# usb-cereal-cp-sch.net
KiCad netlist of a schematic drawn in Altium Designer
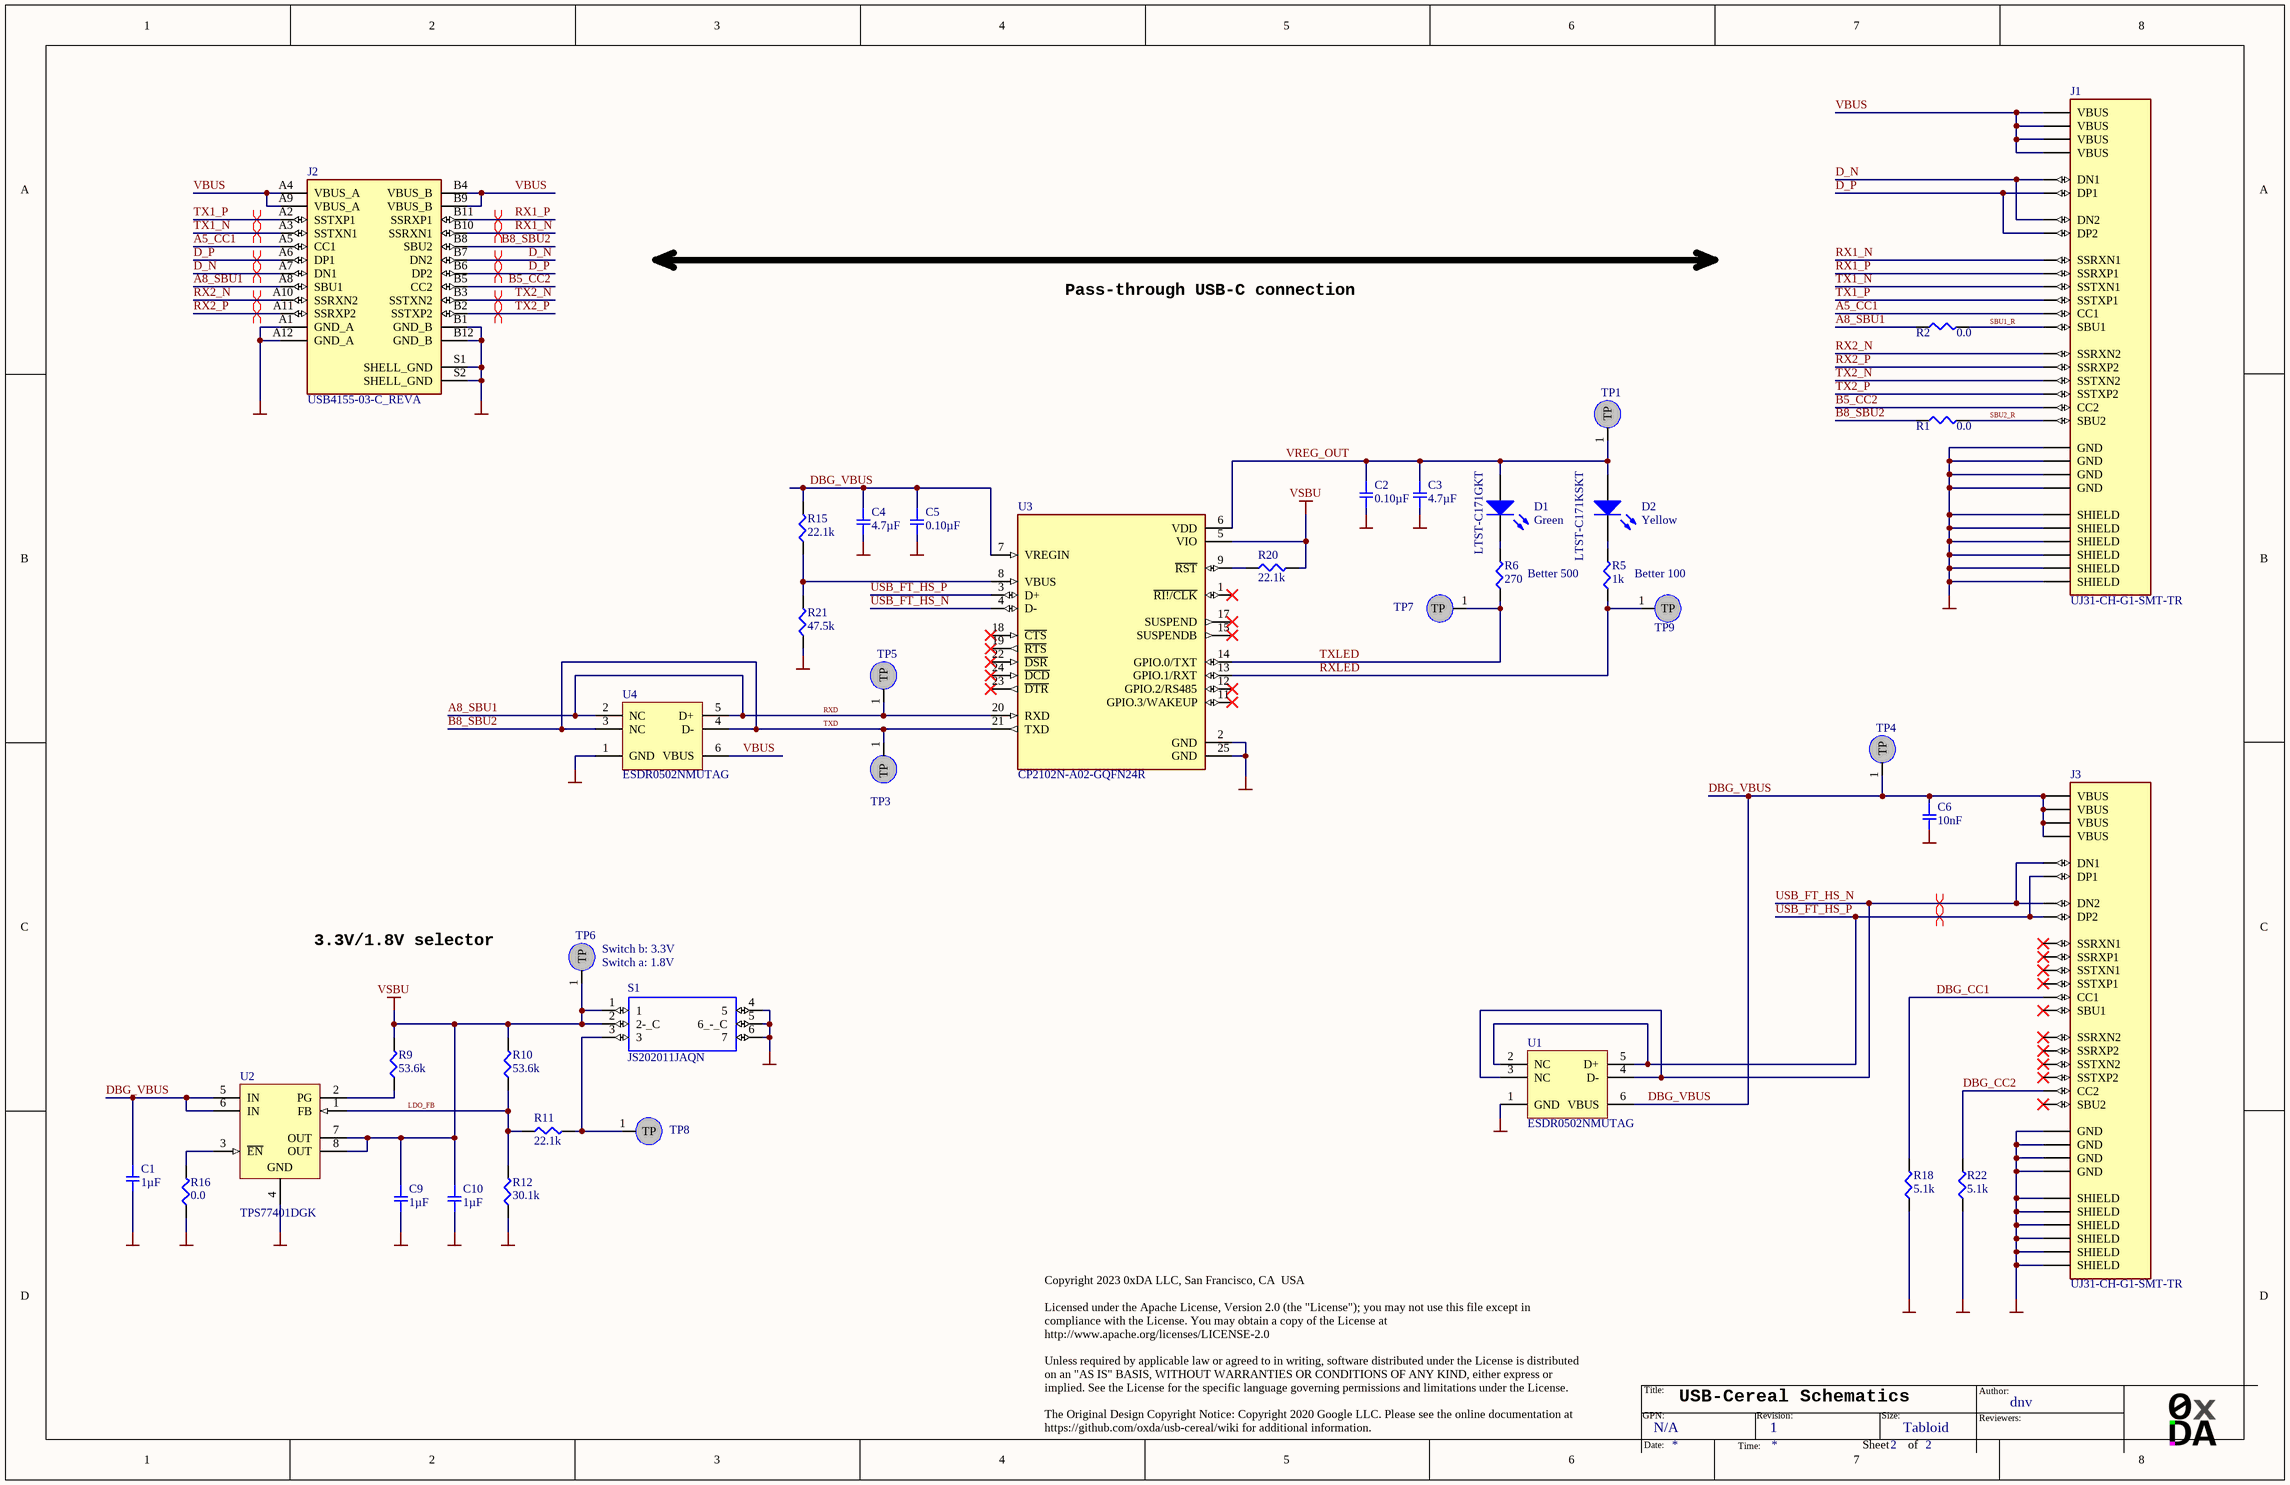
[diagram p0: usb-cereal-cp-sch.SchDoc]

(export (version "E")
  (design (tool "Eeschema 10.0.6"))
  (components
    (comp (ref "C1")
      (value "1µF")
      (footprint "SMD-0402C")
      (description "CAP CER 1UF 10V X7S 0402")
      (fields
        (field (name "DIGI-KEY PART NUMBER") "490-13409-1-ND")
        (field (name "PART NUMBER") "GCM155C71A105KE38D")
      )
      (libsource (lib "cap_murata_0402") (part "GCM155C71A105KE38D"))
    )
    (comp (ref "C2")
      (value "0.10µF")
      (footprint "SMD-0402C")
      (description "CAP CER 0.1UF 10V X5R 0402")
      (fields
        (field (name "DIGI-KEY PART NUMBER") "490-10008-1-ND")
        (field (name "PART NUMBER") "GRM152R61A104KE19D")
      )
      (libsource (lib "cap_murata_0402") (part "GRM152R61A104KE19D"))
    )
    (comp (ref "C3")
      (value "4.7µF")
      (footprint "SMD-0402C")
      (description "CAP CER 4.7UF 10V X5R 0402")
      (fields
        (field (name "DIGI-KEY PART NUMBER") "490-13252-1-ND")
        (field (name "PART NUMBER") "ZRB15XR61A475KE01D")
      )
      (libsource (lib "cap_murata_0402") (part "ZRB15XR61A475KE01D"))
    )
    (comp (ref "C4")
      (value "4.7µF")
      (footprint "SMD-0402C")
      (description "CAP CER 4.7UF 10V X5R 0402")
      (fields
        (field (name "DIGI-KEY PART NUMBER") "490-13252-1-ND")
        (field (name "PART NUMBER") "ZRB15XR61A475KE01D")
      )
      (libsource (lib "cap_murata_0402") (part "ZRB15XR61A475KE01D"))
    )
    (comp (ref "C5")
      (value "0.10µF")
      (footprint "SMD-0402C")
      (description "CAP CER 0.1UF 10V X5R 0402")
      (fields
        (field (name "DIGI-KEY PART NUMBER") "490-10008-1-ND")
        (field (name "PART NUMBER") "GRM152R61A104KE19D")
      )
      (libsource (lib "cap_murata_0402") (part "GRM152R61A104KE19D"))
    )
    (comp (ref "C6")
      (value "10nF")
      (footprint "SMD-0402C")
      (description "CAP CER 10000PF 25V X7R 0402")
      (fields
        (field (name "DIGI-KEY PART NUMBER") "490-6043-1-ND")
        (field (name "PART NUMBER") "GCM155R71E103KA37D")
      )
      (libsource (lib "cap_murata_0402") (part "GCM155R71E103KA37D"))
    )
    (comp (ref "C9")
      (value "1µF")
      (footprint "SMD-0402C")
      (description "CAP CER 1UF 10V X7S 0402")
      (fields
        (field (name "DIGI-KEY PART NUMBER") "490-13409-1-ND")
        (field (name "PART NUMBER") "GCM155C71A105KE38D")
      )
      (libsource (lib "cap_murata_0402") (part "GCM155C71A105KE38D"))
    )
    (comp (ref "C10")
      (value "1µF")
      (footprint "SMD-0402C")
      (description "CAP CER 1UF 10V X7S 0402")
      (fields
        (field (name "DIGI-KEY PART NUMBER") "490-13409-1-ND")
        (field (name "PART NUMBER") "GCM155C71A105KE38D")
      )
      (libsource (lib "cap_murata_0402") (part "GCM155C71A105KE38D"))
    )
    (comp (ref "D1")
      (value "LTST-C171GKT")
      (footprint "0805")
      (description "LED")
      (fields (field (name "COLOR") "Green"))
      (libsource (lib "lite-on") (part "LTST-C171GKT"))
    )
    (comp (ref "D2")
      (value "LTST-C171KSKT")
      (footprint "0805")
      (description "LED")
      (fields (field (name "COLOR") "Yellow"))
      (libsource (lib "lite-on") (part "LTST-C171KSKT"))
    )
    (comp (ref "J1")
      (value "UJ31-CH-G1-SMT-TR")
      (footprint "SnapEDApcb:CUI_UJ31-CH-G1-SMT-TR")
      (description "Type C, USB 3.1 Gen 2, 5 A, Right Angle, Surface Mount _SMT_ , USB Receptacle")
      (fields (field (name "MF") "CUI Devices"))
      (libsource (lib "UJ31-CH-G1-SMT-TR") (part "UJ31-CH-G1-SMT-TR"))
    )
    (comp (ref "J2")
      (value "USB4155-03-C_REVA")
      (footprint "GCT_USB4155-03-C_REVA")
      (fields (field (name "MF") "Global Connector Technology") (field (name "MP") "USB4155-03-C"))
      (libsource (lib "USB4155-03-C_REVA") (part "USB4155-03-C_REVA"))
    )
    (comp (ref "J3")
      (value "UJ31-CH-G1-SMT-TR")
      (footprint "SnapEDApcb:CUI_UJ31-CH-G1-SMT-TR")
      (description "Type C, USB 3.1 Gen 2, 5 A, Right Angle, Surface Mount _SMT_ , USB Receptacle")
      (fields (field (name "MF") "CUI Devices"))
      (libsource (lib "UJ31-CH-G1-SMT-TR") (part "UJ31-CH-G1-SMT-TR"))
    )
    (comp (ref "R1")
      (value "0.0")
      (footprint "SMD-0402-RES")
      (description "RES SMD 0.0OHM JUMPER 1/10W 0402")
      (fields (field (name "PART NUMBER") "ERJ-2GE0R00X") (field (name "DIGI-KEY PART NUMBER") "P0.0JCT-ND"))
      (libsource (lib "res_0402_panasonic_ERJ") (part "ERJ-2GE0R00X"))
    )
    (comp (ref "R2")
      (value "0.0")
      (footprint "SMD-0402-RES")
      (description "RES SMD 0.0OHM JUMPER 1/10W 0402")
      (fields (field (name "PART NUMBER") "ERJ-2GE0R00X") (field (name "DIGI-KEY PART NUMBER") "P0.0JCT-ND"))
      (libsource (lib "res_0402_panasonic_ERJ") (part "ERJ-2GE0R00X"))
    )
    (comp (ref "R5")
      (value "1k")
      (footprint "SMD-0402-RES")
      (description "RES SMD 1K OHM 1% 1/5W 0402")
      (fields
        (field (name "PART NUMBER") "ERJ-PA2F1001X")
        (field (name "DIGI-KEY PART NUMBER") "P17224CT-ND")
      )
      (libsource (lib "res_0402_panasonic_ERJ") (part "ERJ-PA2F1001X"))
    )
    (comp (ref "R6")
      (value "270")
      (footprint "SMD-0402-RES")
      (description "RES SMD 270 OHM 1% 1/10W 0402")
      (fields (field (name "PART NUMBER") "ERJ-2RKF2700X") (field (name "DIGI-KEY PART NUMBER") "P270LCT-ND"))
      (libsource (lib "res_0402_panasonic_ERJ") (part "ERJ-2RKF2700X"))
    )
    (comp (ref "R9")
      (value "53.6k")
      (footprint "SMD-0402-RES")
      (description "RES SMD 53.6K OHM 1% 1/10W 0402")
      (fields
        (field (name "PART NUMBER") "ERJ-2RKF5362X")
        (field (name "DIGI-KEY PART NUMBER") "P53.6KLCT-ND")
      )
      (libsource (lib "res_0402_panasonic_ERJ") (part "ERJ-2RKF5362X"))
    )
    (comp (ref "R10")
      (value "53.6k")
      (footprint "SMD-0402-RES")
      (description "RES SMD 53.6K OHM 1% 1/10W 0402")
      (fields
        (field (name "PART NUMBER") "ERJ-2RKF5362X")
        (field (name "DIGI-KEY PART NUMBER") "P53.6KLCT-ND")
      )
      (libsource (lib "res_0402_panasonic_ERJ") (part "ERJ-2RKF5362X"))
    )
    (comp (ref "R11")
      (value "22.1k")
      (footprint "SMD-0402-RES")
      (description "RES SMD 22.1K OHM 1% 1/10W 0402")
      (fields
        (field (name "PART NUMBER") "ERJ-2RKF2212X")
        (field (name "DIGI-KEY PART NUMBER") "P22.1KLCT-ND")
      )
      (libsource (lib "res_0402_panasonic_ERJ") (part "ERJ-2RKF2212X"))
    )
    (comp (ref "R12")
      (value "30.1k")
      (footprint "SMD-0402-RES")
      (description "RES SMD 30.1K OHM 1% 1/10W 0402")
      (fields
        (field (name "PART NUMBER") "ERJ-2RKF3012X")
        (field (name "DIGI-KEY PART NUMBER") "P30.1KLCT-ND")
      )
      (libsource (lib "res_0402_panasonic_ERJ") (part "ERJ-2RKF3012X"))
    )
    (comp (ref "R15")
      (value "22.1k")
      (footprint "SMD-0402-RES")
      (description "RES SMD 22.1K OHM 1% 1/10W 0402")
      (fields
        (field (name "PART NUMBER") "ERJ-2RKF2212X")
        (field (name "DIGI-KEY PART NUMBER") "P22.1KLCT-ND")
      )
      (libsource (lib "res_0402_panasonic_ERJ") (part "ERJ-2RKF2212X"))
    )
    (comp (ref "R16")
      (value "0.0")
      (footprint "SMD-0402-RES")
      (description "RES SMD 0.0OHM JUMPER 1/10W 0402")
      (fields (field (name "PART NUMBER") "ERJ-2GE0R00X") (field (name "DIGI-KEY PART NUMBER") "P0.0JCT-ND"))
      (libsource (lib "res_0402_panasonic_ERJ") (part "ERJ-2GE0R00X"))
    )
    (comp (ref "R18")
      (value "5.1k")
      (footprint "SMD-0402-RES")
      (description "RES SMD 5.1K OHM 1% 1/10W 0402")
      (fields
        (field (name "PART NUMBER") "ERJ-2RKF5101X")
        (field (name "DIGI-KEY PART NUMBER") "P5.10KLCT-ND")
      )
      (libsource (lib "res_0402_panasonic_ERJ") (part "ERJ-2RKF5101X"))
    )
    (comp (ref "R20")
      (value "22.1k")
      (footprint "SMD-0402-RES")
      (description "RES SMD 22.1K OHM 1% 1/10W 0402")
      (fields
        (field (name "PART NUMBER") "ERJ-2RKF2212X")
        (field (name "DIGI-KEY PART NUMBER") "P22.1KLCT-ND")
      )
      (libsource (lib "res_0402_panasonic_ERJ") (part "ERJ-2RKF2212X"))
    )
    (comp (ref "R21")
      (value "47.5k")
      (footprint "SMD-0402-RES")
      (description "RES SMD 47.5K OHM 1% 1/10W 0402")
      (fields
        (field (name "PART NUMBER") "ERJ-2RKF4752X")
        (field (name "DIGI-KEY PART NUMBER") "P47.5KLCT-ND")
      )
      (libsource (lib "res_0402_panasonic_ERJ") (part "ERJ-2RKF4752X"))
    )
    (comp (ref "R22")
      (value "5.1k")
      (footprint "SMD-0402-RES")
      (description "RES SMD 5.1K OHM 1% 1/10W 0402")
      (fields
        (field (name "PART NUMBER") "ERJ-2RKF5101X")
        (field (name "DIGI-KEY PART NUMBER") "P5.10KLCT-ND")
      )
      (libsource (lib "res_0402_panasonic_ERJ") (part "ERJ-2RKF5101X"))
    )
    (comp (ref "S1")
      (value "JS202011JAQN")
      (footprint "JS202011JAQN")
      (description "Slide Switch DPDT Surface Mount, Right Angle")
      (fields (field (name "MF") "C&K"))
      (libsource (lib "JS202011JAQN") (part "JS202011JAQN"))
    )
    (comp (ref "TP1") (value "GND") (footprint "Testpoint") (libsource (lib "Misc") (part "Testpoint")))
    (comp (ref "TP3") (value "GND") (footprint "Testpoint") (libsource (lib "Misc") (part "Testpoint")))
    (comp (ref "TP4") (value "GND") (footprint "Testpoint") (libsource (lib "Misc") (part "Testpoint")))
    (comp (ref "TP5") (value "GND") (footprint "Testpoint") (libsource (lib "Misc") (part "Testpoint")))
    (comp (ref "TP6") (value "GND") (footprint "Testpoint") (libsource (lib "Misc") (part "Testpoint")))
    (comp (ref "TP7") (value "GND") (footprint "Testpoint") (libsource (lib "Misc") (part "Testpoint")))
    (comp (ref "TP8") (value "GND") (footprint "Testpoint") (libsource (lib "Misc") (part "Testpoint")))
    (comp (ref "TP9") (value "GND") (footprint "Testpoint") (libsource (lib "Misc") (part "Testpoint")))
    (comp (ref "U1")
      (value "ESDR0502NMUTAG")
      (footprint "ONSC-UDFN-6-517AA-01_V")
      (fields (field (name "MANUFACTURER") "On Semiconductor"))
      (libsource (lib "diode_esd_ON_Semi") (part "ESDR0502NMUTAG"))
    )
    (comp (ref "U2")
      (value "TPS77401DGK")
      (footprint "TI-DGK8_N")
      (fields (field (name "MANUFACTURER") "Texas Instruments"))
      (libsource (lib "ic_pwr_ldo_TI_single_channel_ldo_0-350mA") (part "TPS77401DGK"))
    )
    (comp (ref "U3")
      (value "CP2102N-A02-GQFN24R")
      (footprint "QFN50P400X400X80-25N")
      (description "USB Bridge, USB to UART USB 2.0 UART Interface 24-QFN _4x4_")
      (fields (field (name "MF") "Silicon Labs"))
      (libsource (lib "CP2102N-A02-GQFN24R") (part "CP2102N-A02-GQFN24R"))
    )
    (comp (ref "U4")
      (value "ESDR0502NMUTAG")
      (footprint "ONSC-UDFN-6-517AA-01_V")
      (fields (field (name "MANUFACTURER") "On Semiconductor"))
      (libsource (lib "diode_esd_ON_Semi") (part "ESDR0502NMUTAG"))
    )
  )
  (nets
    (net (code "1") (name "/A5_CC1") (class "Default")
      (node (ref "J1") (pin "A5") (pinfunction "CC1_A5") (pintype "bidirectional"))
      (node (ref "J2") (pin "A5") (pinfunction "CC1_A5") (pintype "bidirectional"))
    )
    (net (code "2") (name "/A8_SBU1") (class "Default")
      (node (ref "J2") (pin "A8") (pinfunction "SBU1_A8") (pintype "bidirectional"))
      (node (ref "R2") (pin "1") (pinfunction "1_1") (pintype "passive"))
      (node (ref "TP5") (pin "1") (pinfunction "TP_1") (pintype "passive"))
      (node (ref "U3") (pin "20") (pinfunction "RXD_20") (pintype "input"))
      (node (ref "U4") (pin "2") (pinfunction "NC_2") (pintype "passive"))
      (node (ref "U4") (pin "5") (pinfunction "D+_5") (pintype "passive"))
    )
    (net (code "3") (name "/B5_CC2") (class "Default")
      (node (ref "J1") (pin "B5") (pinfunction "CC2_B5") (pintype "bidirectional"))
      (node (ref "J2") (pin "B5") (pinfunction "CC2_B5") (pintype "bidirectional"))
    )
    (net (code "4") (name "/B8_SBU2") (class "Default")
      (node (ref "J2") (pin "B8") (pinfunction "SBU2_B8") (pintype "bidirectional"))
      (node (ref "R1") (pin "1") (pinfunction "1_1") (pintype "passive"))
      (node (ref "TP3") (pin "1") (pinfunction "TP_1") (pintype "passive"))
      (node (ref "U3") (pin "21") (pinfunction "TXD_21") (pintype "output"))
      (node (ref "U4") (pin "3") (pinfunction "NC_3") (pintype "passive"))
      (node (ref "U4") (pin "4") (pinfunction "D-_4") (pintype "passive"))
    )
    (net (code "5") (name "/DBG_CC1") (class "Default")
      (node (ref "J3") (pin "A5") (pinfunction "CC1_A5") (pintype "bidirectional"))
      (node (ref "R18") (pin "2") (pinfunction "2_2") (pintype "passive"))
    )
    (net (code "6") (name "/DBG_CC2") (class "Default")
      (node (ref "J3") (pin "B5") (pinfunction "CC2_B5") (pintype "bidirectional"))
      (node (ref "R22") (pin "2") (pinfunction "2_2") (pintype "passive"))
    )
    (net (code "7") (name "/DBG_VBUS") (class "Default")
      (node (ref "C1") (pin "1") (pinfunction "1_1") (pintype "passive"))
      (node (ref "C4") (pin "1") (pinfunction "1_1") (pintype "passive"))
      (node (ref "C5") (pin "1") (pinfunction "1_1") (pintype "passive"))
      (node (ref "C6") (pin "1") (pinfunction "1_1") (pintype "passive"))
      (node (ref "J3") (pin "A4") (pinfunction "VBUS_A4") (pintype "power_in"))
      (node (ref "J3") (pin "A9") (pinfunction "VBUS_A9") (pintype "power_in"))
      (node (ref "J3") (pin "B4") (pinfunction "VBUS_B4") (pintype "power_in"))
      (node (ref "J3") (pin "B9") (pinfunction "VBUS_B9") (pintype "power_in"))
      (node (ref "R15") (pin "2") (pinfunction "2_2") (pintype "passive"))
      (node (ref "TP4") (pin "1") (pinfunction "TP_1") (pintype "passive"))
      (node (ref "U1") (pin "6") (pinfunction "VBUS_6") (pintype "power_in"))
      (node (ref "U2") (pin "5") (pinfunction "IN_5") (pintype "power_in"))
      (node (ref "U2") (pin "6") (pinfunction "IN_6") (pintype "power_in"))
      (node (ref "U3") (pin "7") (pinfunction "VREGIN_7") (pintype "input"))
    )
    (net (code "8") (name "/D_N") (class "Default")
      (node (ref "J1") (pin "A7") (pinfunction "DN1_A7") (pintype "bidirectional"))
      (node (ref "J1") (pin "B7") (pinfunction "DN2_B7") (pintype "bidirectional"))
      (node (ref "J2") (pin "A7") (pinfunction "DN1_A7") (pintype "bidirectional"))
      (node (ref "J2") (pin "B7") (pinfunction "DN2_B7") (pintype "bidirectional"))
    )
    (net (code "9") (name "/D_P") (class "Default")
      (node (ref "J1") (pin "A6") (pinfunction "DP1_A6") (pintype "bidirectional"))
      (node (ref "J1") (pin "B6") (pinfunction "DP2_B6") (pintype "bidirectional"))
      (node (ref "J2") (pin "A6") (pinfunction "DP1_A6") (pintype "bidirectional"))
      (node (ref "J2") (pin "B6") (pinfunction "DP2_B6") (pintype "bidirectional"))
    )
    (net (code "10") (name "/LDO_FB") (class "Default")
      (node (ref "R10") (pin "1") (pinfunction "1_1") (pintype "passive"))
      (node (ref "R11") (pin "1") (pinfunction "1_1") (pintype "passive"))
      (node (ref "R12") (pin "2") (pinfunction "2_2") (pintype "passive"))
      (node (ref "U2") (pin "1") (pinfunction "FB_1") (pintype "input"))
    )
    (net (code "11") (name "/RX1_N") (class "Default")
      (node (ref "J1") (pin "B10") (pinfunction "SSRXN1_B10") (pintype "bidirectional"))
      (node (ref "J2") (pin "B10") (pinfunction "SSRXN1_B10") (pintype "bidirectional"))
    )
    (net (code "12") (name "/RX1_P") (class "Default")
      (node (ref "J1") (pin "B11") (pinfunction "SSRXP1_B11") (pintype "bidirectional"))
      (node (ref "J2") (pin "B11") (pinfunction "SSRXP1_B11") (pintype "bidirectional"))
    )
    (net (code "13") (name "/RX2_N") (class "Default")
      (node (ref "J1") (pin "A10") (pinfunction "SSRXN2_A10") (pintype "bidirectional"))
      (node (ref "J2") (pin "A10") (pinfunction "SSRXN2_A10") (pintype "bidirectional"))
    )
    (net (code "14") (name "/RX2_P") (class "Default")
      (node (ref "J1") (pin "A11") (pinfunction "SSRXP2_A11") (pintype "bidirectional"))
      (node (ref "J2") (pin "A11") (pinfunction "SSRXP2_A11") (pintype "bidirectional"))
    )
    (net (code "15") (name "/RXLED") (class "Default")
      (node (ref "R5") (pin "1") (pinfunction "1_1") (pintype "passive"))
      (node (ref "TP9") (pin "1") (pinfunction "TP_1") (pintype "passive"))
      (node (ref "U3") (pin "13") (pinfunction "GPIO.1/RXT_13") (pintype "bidirectional"))
    )
    (net (code "16") (name "/SBU1_R") (class "Default")
      (node (ref "J1") (pin "A8") (pinfunction "SBU1_A8") (pintype "bidirectional"))
      (node (ref "R2") (pin "2") (pinfunction "2_2") (pintype "passive"))
    )
    (net (code "17") (name "/SBU2_R") (class "Default")
      (node (ref "J1") (pin "B8") (pinfunction "SBU2_B8") (pintype "bidirectional"))
      (node (ref "R1") (pin "2") (pinfunction "2_2") (pintype "passive"))
    )
    (net (code "18") (name "/TX1_N") (class "Default")
      (node (ref "J1") (pin "A3") (pinfunction "SSTXN1_A3") (pintype "bidirectional"))
      (node (ref "J2") (pin "A3") (pinfunction "SSTXN1_A3") (pintype "bidirectional"))
    )
    (net (code "19") (name "/TX1_P") (class "Default")
      (node (ref "J1") (pin "A2") (pinfunction "SSTXP1_A2") (pintype "bidirectional"))
      (node (ref "J2") (pin "A2") (pinfunction "SSTXP1_A2") (pintype "bidirectional"))
    )
    (net (code "20") (name "/TX2_N") (class "Default")
      (node (ref "J1") (pin "B3") (pinfunction "SSTXN2_B3") (pintype "bidirectional"))
      (node (ref "J2") (pin "B3") (pinfunction "SSTXN2_B3") (pintype "bidirectional"))
    )
    (net (code "21") (name "/TX2_P") (class "Default")
      (node (ref "J1") (pin "B2") (pinfunction "SSTXP2_B2") (pintype "bidirectional"))
      (node (ref "J2") (pin "B2") (pinfunction "SSTXP2_B2") (pintype "bidirectional"))
    )
    (net (code "22") (name "/TXLED") (class "Default")
      (node (ref "R6") (pin "1") (pinfunction "1_1") (pintype "passive"))
      (node (ref "TP7") (pin "1") (pinfunction "TP_1") (pintype "passive"))
      (node (ref "U3") (pin "14") (pinfunction "GPIO.0/TXT_14") (pintype "bidirectional"))
    )
    (net (code "23") (name "/USB_FT_HS_N") (class "Default")
      (node (ref "J3") (pin "A7") (pinfunction "DN1_A7") (pintype "bidirectional"))
      (node (ref "J3") (pin "B7") (pinfunction "DN2_B7") (pintype "bidirectional"))
      (node (ref "U1") (pin "3") (pinfunction "NC_3") (pintype "passive"))
      (node (ref "U1") (pin "4") (pinfunction "D-_4") (pintype "passive"))
      (node (ref "U3") (pin "4") (pinfunction "D-_4") (pintype "bidirectional"))
    )
    (net (code "24") (name "/USB_FT_HS_P") (class "Default")
      (node (ref "J3") (pin "A6") (pinfunction "DP1_A6") (pintype "bidirectional"))
      (node (ref "J3") (pin "B6") (pinfunction "DP2_B6") (pintype "bidirectional"))
      (node (ref "U1") (pin "2") (pinfunction "NC_2") (pintype "passive"))
      (node (ref "U1") (pin "5") (pinfunction "D+_5") (pintype "passive"))
      (node (ref "U3") (pin "3") (pinfunction "D+_3") (pintype "bidirectional"))
    )
    (net (code "25") (name "/VBUS") (class "Default")
      (node (ref "J1") (pin "A4") (pinfunction "VBUS_A4") (pintype "power_in"))
      (node (ref "J1") (pin "A9") (pinfunction "VBUS_A9") (pintype "power_in"))
      (node (ref "J1") (pin "B4") (pinfunction "VBUS_B4") (pintype "power_in"))
      (node (ref "J1") (pin "B9") (pinfunction "VBUS_B9") (pintype "power_in"))
      (node (ref "J2") (pin "A4") (pinfunction "VBUS_A_A4") (pintype "power_in"))
      (node (ref "J2") (pin "A9") (pinfunction "VBUS_A_A9") (pintype "power_in"))
      (node (ref "J2") (pin "B4") (pinfunction "VBUS_B_B4") (pintype "power_in"))
      (node (ref "J2") (pin "B9") (pinfunction "VBUS_B_B9") (pintype "power_in"))
      (node (ref "U4") (pin "6") (pinfunction "VBUS_6") (pintype "power_in"))
    )
    (net (code "26") (name "/VREG_OUT") (class "Default")
      (node (ref "C2") (pin "1") (pinfunction "1_1") (pintype "passive"))
      (node (ref "C3") (pin "1") (pinfunction "1_1") (pintype "passive"))
      (node (ref "D1") (pin "1") (pinfunction "A_1") (pintype "passive"))
      (node (ref "D2") (pin "1") (pinfunction "A_1") (pintype "passive"))
      (node (ref "TP1") (pin "1") (pinfunction "TP_1") (pintype "passive"))
      (node (ref "U3") (pin "6") (pinfunction "VDD_6") (pintype "power_in"))
    )
    (net (code "27") (name "GND") (class "Default")
      (node (ref "C1") (pin "2") (pinfunction "2_2") (pintype "passive"))
      (node (ref "C10") (pin "2") (pinfunction "2_2") (pintype "passive"))
      (node (ref "C2") (pin "2") (pinfunction "2_2") (pintype "passive"))
      (node (ref "C3") (pin "2") (pinfunction "2_2") (pintype "passive"))
      (node (ref "C4") (pin "2") (pinfunction "2_2") (pintype "passive"))
      (node (ref "C5") (pin "2") (pinfunction "2_2") (pintype "passive"))
      (node (ref "C6") (pin "2") (pinfunction "2_2") (pintype "passive"))
      (node (ref "C9") (pin "2") (pinfunction "2_2") (pintype "passive"))
      (node (ref "J1") (pin "A1") (pinfunction "GND_A1") (pintype "power_in"))
      (node (ref "J1") (pin "A12") (pinfunction "GND_A12") (pintype "power_in"))
      (node (ref "J1") (pin "B1") (pinfunction "GND_B1") (pintype "power_in"))
      (node (ref "J1") (pin "B12") (pinfunction "GND_B12") (pintype "power_in"))
      (node (ref "J1") (pin "SH1") (pinfunction "SHIELD_SH1") (pintype "power_in"))
      (node (ref "J1") (pin "SH2") (pinfunction "SHIELD_SH2") (pintype "power_in"))
      (node (ref "J1") (pin "SH3") (pinfunction "SHIELD_SH3") (pintype "power_in"))
      (node (ref "J1") (pin "SH4") (pinfunction "SHIELD_SH4") (pintype "power_in"))
      (node (ref "J1") (pin "SH5") (pinfunction "SHIELD_SH5") (pintype "power_in"))
      (node (ref "J1") (pin "SH6") (pinfunction "SHIELD_SH6") (pintype "power_in"))
      (node (ref "J2") (pin "A1") (pinfunction "GND_A_A1") (pintype "power_in"))
      (node (ref "J2") (pin "A12") (pinfunction "GND_A_A12") (pintype "power_in"))
      (node (ref "J2") (pin "B1") (pinfunction "GND_B_B1") (pintype "power_in"))
      (node (ref "J2") (pin "B12") (pinfunction "GND_B_B12") (pintype "power_in"))
      (node (ref "J2") (pin "S1") (pinfunction "SHELL_GND_S1") (pintype "power_in"))
      (node (ref "J2") (pin "S2") (pinfunction "SHELL_GND_S2") (pintype "power_in"))
      (node (ref "J3") (pin "A1") (pinfunction "GND_A1") (pintype "power_in"))
      (node (ref "J3") (pin "A12") (pinfunction "GND_A12") (pintype "power_in"))
      (node (ref "J3") (pin "B1") (pinfunction "GND_B1") (pintype "power_in"))
      (node (ref "J3") (pin "B12") (pinfunction "GND_B12") (pintype "power_in"))
      (node (ref "J3") (pin "SH1") (pinfunction "SHIELD_SH1") (pintype "power_in"))
      (node (ref "J3") (pin "SH2") (pinfunction "SHIELD_SH2") (pintype "power_in"))
      (node (ref "J3") (pin "SH3") (pinfunction "SHIELD_SH3") (pintype "power_in"))
      (node (ref "J3") (pin "SH4") (pinfunction "SHIELD_SH4") (pintype "power_in"))
      (node (ref "J3") (pin "SH5") (pinfunction "SHIELD_SH5") (pintype "power_in"))
      (node (ref "J3") (pin "SH6") (pinfunction "SHIELD_SH6") (pintype "power_in"))
      (node (ref "R12") (pin "1") (pinfunction "1_1") (pintype "passive"))
      (node (ref "R16") (pin "1") (pinfunction "1_1") (pintype "passive"))
      (node (ref "R18") (pin "1") (pinfunction "1_1") (pintype "passive"))
      (node (ref "R21") (pin "1") (pinfunction "1_1") (pintype "passive"))
      (node (ref "R22") (pin "1") (pinfunction "1_1") (pintype "passive"))
      (node (ref "S1") (pin "4") (pinfunction "5_4") (pintype "bidirectional"))
      (node (ref "S1") (pin "5") (pinfunction "6_-_C_5") (pintype "bidirectional"))
      (node (ref "S1") (pin "6") (pinfunction "7_6") (pintype "bidirectional"))
      (node (ref "U1") (pin "1") (pinfunction "GND_1") (pintype "power_in"))
      (node (ref "U2") (pin "4") (pinfunction "GND_4") (pintype "power_in"))
      (node (ref "U3") (pin "2") (pinfunction "GND_2") (pintype "power_in"))
      (node (ref "U3") (pin "25") (pinfunction "GND_25") (pintype "power_in"))
      (node (ref "U4") (pin "1") (pinfunction "GND_1") (pintype "power_in"))
    )
    (net (code "28") (name "Net-(D1-K)") (class "Default")
      (node (ref "D1") (pin "2") (pinfunction "K_2") (pintype "passive"))
      (node (ref "R6") (pin "2") (pinfunction "2_2") (pintype "passive"))
    )
    (net (code "29") (name "Net-(D2-K)") (class "Default")
      (node (ref "D2") (pin "2") (pinfunction "K_2") (pintype "passive"))
      (node (ref "R5") (pin "2") (pinfunction "2_2") (pintype "passive"))
    )
    (net (code "30") (name "Net-(TP8-TP)") (class "Default")
      (node (ref "R11") (pin "2") (pinfunction "2_2") (pintype "passive"))
      (node (ref "S1") (pin "3") (pinfunction "3_3") (pintype "bidirectional"))
      (node (ref "TP8") (pin "1") (pinfunction "TP_1") (pintype "passive"))
    )
    (net (code "31") (name "Net-(U2-PG)") (class "Default")
      (node (ref "R9") (pin "1") (pinfunction "1_1") (pintype "passive"))
      (node (ref "U2") (pin "2") (pinfunction "PG_2") (pintype "tri_state"))
    )
    (net (code "32") (name "Net-(U2-~{EN})") (class "Default")
      (node (ref "R16") (pin "2") (pinfunction "2_2") (pintype "passive"))
      (node (ref "U2") (pin "3") (pinfunction "~{EN}_3") (pintype "input"))
    )
    (net (code "33") (name "Net-(U3-VBUS)") (class "Default")
      (node (ref "R15") (pin "1") (pinfunction "1_1") (pintype "passive"))
      (node (ref "R21") (pin "2") (pinfunction "2_2") (pintype "passive"))
      (node (ref "U3") (pin "8") (pinfunction "VBUS_8") (pintype "input"))
    )
    (net (code "34") (name "Net-(U3-~{RST})") (class "Default")
      (node (ref "R20") (pin "1") (pinfunction "1_1") (pintype "passive"))
      (node (ref "U3") (pin "9") (pinfunction "~{RST}_9") (pintype "bidirectional"))
    )
    (net (code "35") (name "VSBU") (class "Default")
      (node (ref "C10") (pin "1") (pinfunction "1_1") (pintype "passive"))
      (node (ref "C9") (pin "1") (pinfunction "1_1") (pintype "passive"))
      (node (ref "R10") (pin "2") (pinfunction "2_2") (pintype "passive"))
      (node (ref "R20") (pin "2") (pinfunction "2_2") (pintype "passive"))
      (node (ref "R9") (pin "2") (pinfunction "2_2") (pintype "passive"))
      (node (ref "S1") (pin "1") (pinfunction "1_1") (pintype "bidirectional"))
      (node (ref "S1") (pin "2") (pinfunction "2-_C_2") (pintype "bidirectional"))
      (node (ref "TP6") (pin "1") (pinfunction "TP_1") (pintype "passive"))
      (node (ref "U2") (pin "7") (pinfunction "OUT_7") (pintype "power_in"))
      (node (ref "U2") (pin "8") (pinfunction "OUT_8") (pintype "power_in"))
      (node (ref "U3") (pin "5") (pinfunction "VIO_5") (pintype "power_in"))
    )
    (net (code "36") (name "unconnected-(J3-SBU1-PadA8)") (class "Default")
      (node (ref "J3") (pin "A8") (pinfunction "SBU1_A8") (pintype "bidirectional+no_connect"))
    )
    (net (code "37") (name "unconnected-(J3-SBU2-PadB8)") (class "Default")
      (node (ref "J3") (pin "B8") (pinfunction "SBU2_B8") (pintype "bidirectional+no_connect"))
    )
    (net (code "38") (name "unconnected-(J3-SSRXN1-PadB10)") (class "Default")
      (node (ref "J3") (pin "B10") (pinfunction "SSRXN1_B10") (pintype "bidirectional+no_connect"))
    )
    (net (code "39") (name "unconnected-(J3-SSRXN2-PadA10)") (class "Default")
      (node (ref "J3") (pin "A10") (pinfunction "SSRXN2_A10") (pintype "bidirectional+no_connect"))
    )
    (net (code "40") (name "unconnected-(J3-SSRXP1-PadB11)") (class "Default")
      (node (ref "J3") (pin "B11") (pinfunction "SSRXP1_B11") (pintype "bidirectional+no_connect"))
    )
    (net (code "41") (name "unconnected-(J3-SSRXP2-PadA11)") (class "Default")
      (node (ref "J3") (pin "A11") (pinfunction "SSRXP2_A11") (pintype "bidirectional+no_connect"))
    )
    (net (code "42") (name "unconnected-(J3-SSTXN1-PadA3)") (class "Default")
      (node (ref "J3") (pin "A3") (pinfunction "SSTXN1_A3") (pintype "bidirectional+no_connect"))
    )
    (net (code "43") (name "unconnected-(J3-SSTXN2-PadB3)") (class "Default")
      (node (ref "J3") (pin "B3") (pinfunction "SSTXN2_B3") (pintype "bidirectional+no_connect"))
    )
    (net (code "44") (name "unconnected-(J3-SSTXP1-PadA2)") (class "Default")
      (node (ref "J3") (pin "A2") (pinfunction "SSTXP1_A2") (pintype "bidirectional+no_connect"))
    )
    (net (code "45") (name "unconnected-(J3-SSTXP2-PadB2)") (class "Default")
      (node (ref "J3") (pin "B2") (pinfunction "SSTXP2_B2") (pintype "bidirectional+no_connect"))
    )
    (net (code "46") (name "unconnected-(U3-GPIO.2{slash}RS485-Pad12)") (class "Default")
      (node (ref "U3") (pin "12") (pinfunction "GPIO.2/RS485_12") (pintype "bidirectional+no_connect"))
    )
    (net (code "47") (name "unconnected-(U3-GPIO.3{slash}WAKEUP-Pad11)") (class "Default")
      (node (ref "U3") (pin "11") (pinfunction "GPIO.3/WAKEUP_11") (pintype "bidirectional+no_connect"))
    )
    (net (code "48") (name "unconnected-(U3-SUSPEND-Pad17)") (class "Default")
      (node (ref "U3") (pin "17") (pinfunction "SUSPEND_17") (pintype "output+no_connect"))
    )
    (net (code "49") (name "unconnected-(U3-SUSPENDB-Pad15)") (class "Default")
      (node (ref "U3") (pin "15") (pinfunction "SUSPENDB_15") (pintype "output+no_connect"))
    )
    (net (code "50") (name "unconnected-(U3-~{CTS}-Pad18)") (class "Default")
      (node (ref "U3") (pin "18") (pinfunction "~{CTS}_18") (pintype "input+no_connect"))
    )
    (net (code "51") (name "unconnected-(U3-~{DCD}-Pad24)") (class "Default")
      (node (ref "U3") (pin "24") (pinfunction "~{DCD}_24") (pintype "input+no_connect"))
    )
    (net (code "52") (name "unconnected-(U3-~{DSR}-Pad22)") (class "Default")
      (node (ref "U3") (pin "22") (pinfunction "~{DSR}_22") (pintype "input+no_connect"))
    )
    (net (code "53") (name "unconnected-(U3-~{DTR}-Pad23)") (class "Default")
      (node (ref "U3") (pin "23") (pinfunction "~{DTR}_23") (pintype "output+no_connect"))
    )
    (net (code "54") (name "unconnected-(U3-~{RI!{slash}CLK}-Pad1)") (class "Default")
      (node (ref "U3") (pin "1") (pinfunction "~{RI!/CLK}_1") (pintype "bidirectional+no_connect"))
    )
    (net (code "55") (name "unconnected-(U3-~{RTS}-Pad19)") (class "Default")
      (node (ref "U3") (pin "19") (pinfunction "~{RTS}_19") (pintype "output+no_connect"))
    )
  )
)
